# pd15.net
KiCad netlist of a schematic drawn in EAGLE
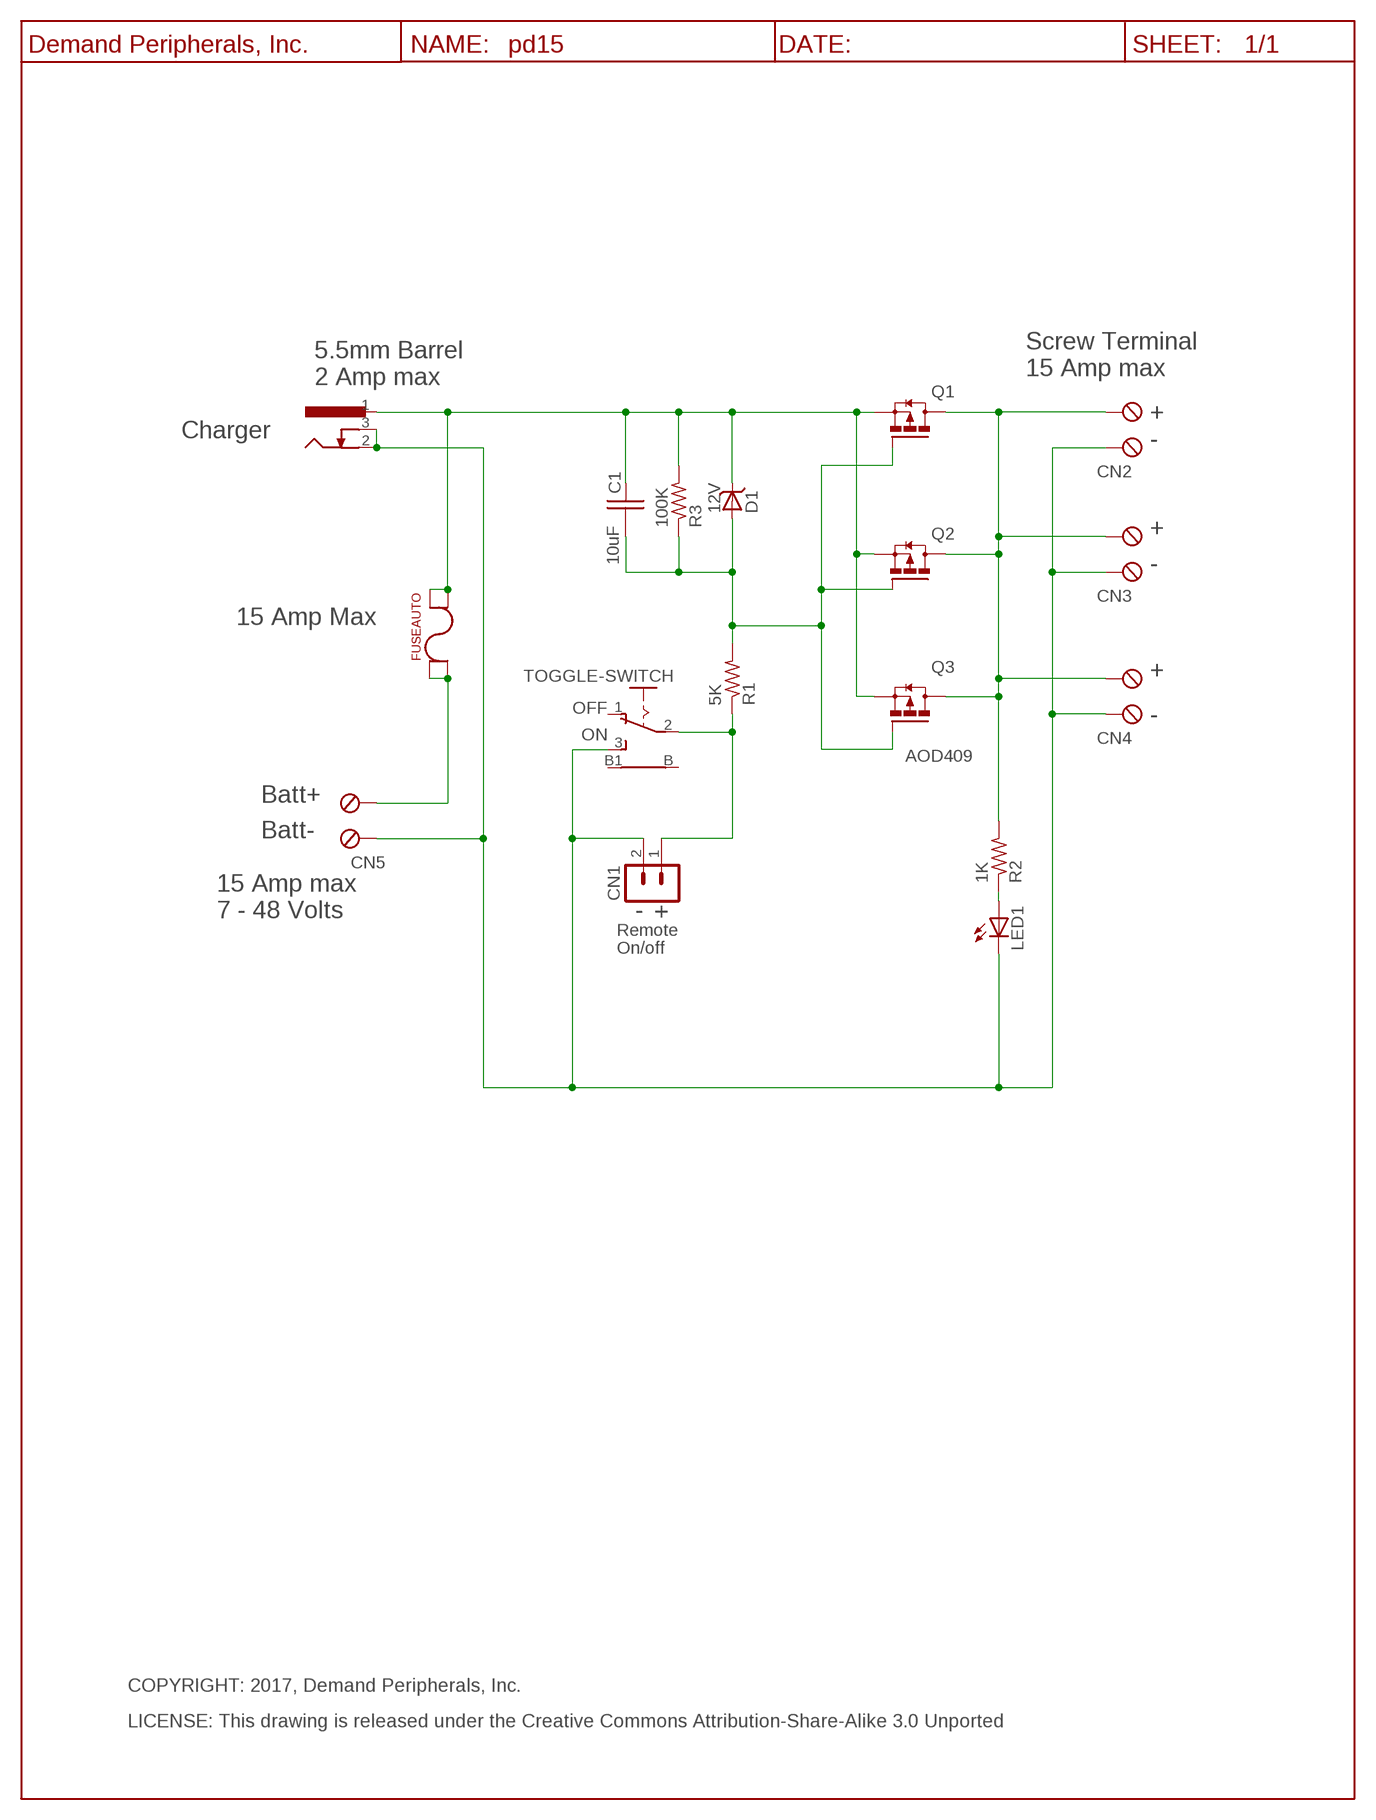
[diagram p0: schematic, sheet 1]

(export (version "E")
  (design (tool "Eeschema 10.0.6"))
  (components
    (comp (ref "C1")
      (value "10uF")
      (footprint "eagle-import:C0805")
      (libsource (lib "eagle-import") (part "C10UF35V_C0805"))
    )
    (comp (ref "CN1")
      (value "HDR-2X1-LCK")
      (footprint "eagle-import:HDR-2X1")
      (libsource (lib "eagle-import") (part "HDR-2X1-LCK"))
    )
    (comp (ref "CN2")
      (value "TBLK-5.08-X2")
      (footprint "eagle-import:TBLK-5.08-X2")
      (libsource (lib "eagle-import") (part "TBLK-5.08-X2"))
    )
    (comp (ref "CN3")
      (value "TBLK-5.08-X2")
      (footprint "eagle-import:TBLK-5.08-X2")
      (libsource (lib "eagle-import") (part "TBLK-5.08-X2"))
    )
    (comp (ref "CN4")
      (value "TBLK-5.08-X2")
      (footprint "eagle-import:TBLK-5.08-X2")
      (libsource (lib "eagle-import") (part "TBLK-5.08-X2"))
    )
    (comp (ref "CN5")
      (value "TBLK-5.08-X2")
      (footprint "eagle-import:TBLK-5.08-X2")
      (libsource (lib "eagle-import") (part "TBLK-5.08-X2"))
    )
    (comp (ref "D1")
      (value "12V")
      (footprint "eagle-import:SOD123")
      (libsource (lib "eagle-import") (part "BZT52C12"))
    )
    (comp (ref "FUSE")
      (value "FUSEAUTO")
      (footprint "eagle-import:KS3557-10")
      (libsource (lib "eagle-import") (part "FUSE-KS3557"))
    )
    (comp (ref "J1")
      (value "Barrel-5.5mm")
      (footprint "eagle-import:DC-BARREL-JACK-55MM")
      (libsource (lib "eagle-import") (part "DC-BARREL-JACK--55MM"))
    )
    (comp (ref "LED1")
      (value "LED-5MM-GRN")
      (footprint "eagle-import:LED5MM")
      (libsource (lib "eagle-import") (part "LED-5MM-GRN"))
    )
    (comp (ref "Q1")
      (value "FET_DPAK_P")
      (footprint "eagle-import:DPACK_TO-252")
      (libsource (lib "eagle-import") (part "AOD409"))
    )
    (comp (ref "Q2")
      (value "FET_DPAK_P")
      (footprint "eagle-import:DPACK_TO-252")
      (libsource (lib "eagle-import") (part "AOD409"))
    )
    (comp (ref "Q3")
      (value "AOD409")
      (footprint "eagle-import:DPACK_TO-252")
      (libsource (lib "eagle-import") (part "AOD409"))
    )
    (comp (ref "R1")
      (value "5K")
      (footprint "eagle-import:R0603")
      (libsource (lib "eagle-import") (part "R4.99K_R0603"))
    )
    (comp (ref "R2")
      (value "1K")
      (footprint "eagle-import:R0603")
      (libsource (lib "eagle-import") (part "R1K_R0603"))
    )
    (comp (ref "R3")
      (value "100K")
      (footprint "eagle-import:R0603")
      (libsource (lib "eagle-import") (part "R100K_R0603"))
    )
    (comp (ref "TOGGLE-SWITCH")
      (value "B12EH")
      (footprint "eagle-import:TOGGLE_SPDT_PC")
      (libsource (lib "eagle-import") (part "TOGGLE_SPDT_PC"))
    )
    (comp (ref "U$1")
      (value "DP_FRAME_P")
      (footprint "eagle-import:LETTER_P")
      (libsource (lib "eagle-import") (part "DP_FRAME_P"))
    )
  )
  (nets
    (net (code "1") (name "Net-(CN1-1)") (class "Default")
      (node (ref "CN1") (pin "2") (pinfunction "1_2") (pintype "passive"))
      (node (ref "CN2") (pin "1") (pinfunction "KL_1") (pintype "passive"))
      (node (ref "CN3") (pin "1") (pinfunction "KL_1") (pintype "passive"))
      (node (ref "CN4") (pin "1") (pinfunction "KL_1") (pintype "passive"))
      (node (ref "CN5") (pin "1") (pinfunction "KL_1") (pintype "passive"))
      (node (ref "J1") (pin "2") (pinfunction "2_2") (pintype "passive"))
      (node (ref "J1") (pin "3") (pinfunction "3_3") (pintype "passive"))
      (node (ref "LED1") (pin "C") (pinfunction "C_C") (pintype "passive"))
      (node (ref "TOGGLE-SWITCH") (pin "3") (pinfunction "S_3") (pintype "passive"))
    )
    (net (code "2") (name "Net-(CN1-2)") (class "Default")
      (node (ref "CN1") (pin "1") (pinfunction "2_1") (pintype "passive"))
      (node (ref "R1") (pin "1") (pinfunction "1_1") (pintype "passive"))
      (node (ref "TOGGLE-SWITCH") (pin "2") (pinfunction "P_2") (pintype "passive"))
    )
    (net (code "3") (name "Net-(CN2-KL1)") (class "Default")
      (node (ref "CN2") (pin "2") (pinfunction "KL1_2") (pintype "passive"))
      (node (ref "CN3") (pin "2") (pinfunction "KL1_2") (pintype "passive"))
      (node (ref "CN4") (pin "2") (pinfunction "KL1_2") (pintype "passive"))
      (node (ref "Q1") (pin "4") (pinfunction "D_4") (pintype "passive"))
      (node (ref "Q2") (pin "4") (pinfunction "D_4") (pintype "passive"))
      (node (ref "Q3") (pin "4") (pinfunction "D_4") (pintype "passive"))
      (node (ref "R2") (pin "2") (pinfunction "2_2") (pintype "passive"))
    )
    (net (code "4") (name "Net-(CN5-KL1)") (class "Default")
      (node (ref "CN5") (pin "2") (pinfunction "KL1_2") (pintype "passive"))
      (node (ref "FUSE") (pin "LS@1") (pinfunction "LS_LS@1") (pintype "power_in"))
      (node (ref "FUSE") (pin "LS@2") (pinfunction "LS_LS@2") (pintype "power_in"))
    )
    (net (code "5") (name "Net-(LED1-PadA)") (class "Default")
      (node (ref "LED1") (pin "A") (pinfunction "A_A") (pintype "passive"))
      (node (ref "R2") (pin "1") (pinfunction "1_1") (pintype "passive"))
    )
    (net (code "6") (name "Net-(Q1-G)") (class "Default")
      (node (ref "C1") (pin "2") (pinfunction "2_2") (pintype "passive"))
      (node (ref "D1") (pin "A") (pinfunction "A_A") (pintype "passive"))
      (node (ref "Q1") (pin "1") (pinfunction "G_1") (pintype "passive"))
      (node (ref "Q2") (pin "1") (pinfunction "G_1") (pintype "passive"))
      (node (ref "Q3") (pin "1") (pinfunction "G_1") (pintype "passive"))
      (node (ref "R1") (pin "2") (pinfunction "2_2") (pintype "passive"))
      (node (ref "R3") (pin "1") (pinfunction "1_1") (pintype "passive"))
    )
    (net (code "7") (name "Net-(Q1-S)") (class "Default")
      (node (ref "C1") (pin "1") (pinfunction "1_1") (pintype "passive"))
      (node (ref "D1") (pin "C") (pinfunction "C_C") (pintype "passive"))
      (node (ref "FUSE") (pin "RS@3") (pinfunction "RS_RS@3") (pintype "power_in"))
      (node (ref "FUSE") (pin "RS@4") (pinfunction "RS_RS@4") (pintype "power_in"))
      (node (ref "J1") (pin "1") (pinfunction "1_1") (pintype "passive"))
      (node (ref "Q1") (pin "3") (pinfunction "S_3") (pintype "passive"))
      (node (ref "Q2") (pin "3") (pinfunction "S_3") (pintype "passive"))
      (node (ref "Q3") (pin "3") (pinfunction "S_3") (pintype "passive"))
      (node (ref "R3") (pin "2") (pinfunction "2_2") (pintype "passive"))
    )
    (net (code "8") (name "unconnected-(TOGGLE-SWITCH-O-Pad1)") (class "Default")
      (node (ref "TOGGLE-SWITCH") (pin "1") (pinfunction "O_1") (pintype "passive"))
    )
    (net (code "9") (name "unconnected-(TOGGLE-SWITCH-PadB)") (class "Default")
      (node (ref "TOGGLE-SWITCH") (pin "B") (pinfunction "B_B") (pintype "passive"))
    )
    (net (code "10") (name "unconnected-(TOGGLE-SWITCH-PadB1)") (class "Default")
      (node (ref "TOGGLE-SWITCH") (pin "B1") (pinfunction "B1_B1") (pintype "passive"))
    )
  )
)
